# Total.net
KiCad netlist of a schematic drawn in Altium Designer
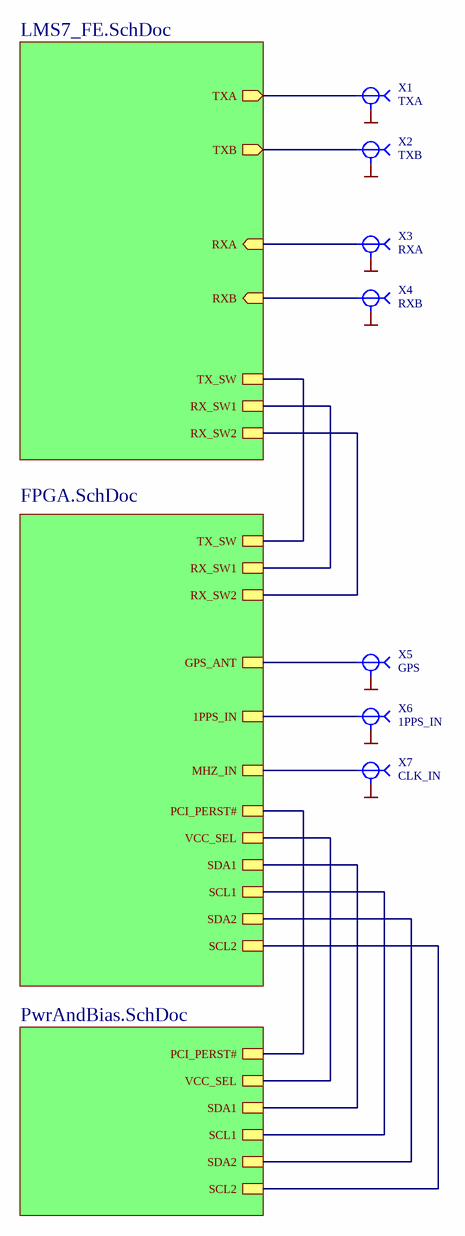
[diagram p0: Total.SchDoc]

(export (version "E")
  (design (tool "Eeschema 10.0.6"))
  (components
    (comp (ref "X1")
      (value "~")
      (footprint "U_FL")
      (description "Connector (UMCC)")
      (fields (field (name "MANUFACTURER") "Molex") (field (name "LABEL") "TXA"))
      (libsource (lib "Andy") (part "U_FL"))
    )
    (comp (ref "X2")
      (value "~")
      (footprint "U_FL")
      (description "Connector (UMCC)")
      (fields (field (name "MANUFACTURER") "Molex") (field (name "LABEL") "TXB"))
      (libsource (lib "Andy") (part "U_FL"))
    )
    (comp (ref "X3")
      (value "~")
      (footprint "U_FL")
      (description "Connector (UMCC)")
      (fields (field (name "MANUFACTURER") "Molex") (field (name "LABEL") "RXA"))
      (libsource (lib "Andy") (part "U_FL"))
    )
    (comp (ref "X4")
      (value "~")
      (footprint "U_FL")
      (description "Connector (UMCC)")
      (fields (field (name "MANUFACTURER") "Molex") (field (name "LABEL") "RXB"))
      (libsource (lib "Andy") (part "U_FL"))
    )
    (comp (ref "X5")
      (value "~")
      (footprint "U_FL")
      (description "Connector (UMCC)")
      (fields (field (name "MANUFACTURER") "Molex") (field (name "LABEL") "GPS"))
      (libsource (lib "Andy") (part "U_FL"))
    )
    (comp (ref "X6")
      (value "~")
      (footprint "U_FL")
      (description "Connector (UMCC)")
      (fields (field (name "MANUFACTURER") "Molex") (field (name "LABEL") "1PPS_IN"))
      (libsource (lib "Andy") (part "U_FL"))
    )
    (comp (ref "X7")
      (value "~")
      (footprint "U_FL")
      (description "Connector (UMCC)")
      (fields (field (name "MANUFACTURER") "Molex") (field (name "LABEL") "CLK_IN"))
      (libsource (lib "Andy") (part "U_FL"))
    )
  )
  (nets
    (net (code "1") (name "/1PPS_IN") (class "Default")
      (node (ref "X6") (pin "1") (pinfunction "1_1") (pintype "passive"))
    )
    (net (code "2") (name "/GPS_ANT") (class "Default")
      (node (ref "X5") (pin "1") (pinfunction "1_1") (pintype "passive"))
    )
    (net (code "3") (name "/MHZ_IN") (class "Default")
      (node (ref "X7") (pin "1") (pinfunction "1_1") (pintype "passive"))
    )
    (net (code "5") (name "/RXA") (class "Default")
      (node (ref "X3") (pin "1") (pinfunction "1_1") (pintype "passive"))
    )
    (net (code "6") (name "/RXB") (class "Default")
      (node (ref "X4") (pin "1") (pinfunction "1_1") (pintype "passive"))
    )
    (net (code "13") (name "/TXA") (class "Default")
      (node (ref "X1") (pin "1") (pinfunction "1_1") (pintype "passive"))
    )
    (net (code "14") (name "/TXB") (class "Default")
      (node (ref "X2") (pin "1") (pinfunction "1_1") (pintype "passive"))
    )
    (net (code "17") (name "GND") (class "Default")
      (node (ref "X1") (pin "2") (pinfunction "GND_2") (pintype "passive"))
      (node (ref "X2") (pin "2") (pinfunction "GND_2") (pintype "passive"))
      (node (ref "X3") (pin "2") (pinfunction "GND_2") (pintype "passive"))
      (node (ref "X4") (pin "2") (pinfunction "GND_2") (pintype "passive"))
      (node (ref "X5") (pin "2") (pinfunction "GND_2") (pintype "passive"))
      (node (ref "X6") (pin "2") (pinfunction "GND_2") (pintype "passive"))
      (node (ref "X7") (pin "2") (pinfunction "GND_2") (pintype "passive"))
    )
  )
)
